# untitled.net
KiCad netlist of a schematic drawn in EAGLE
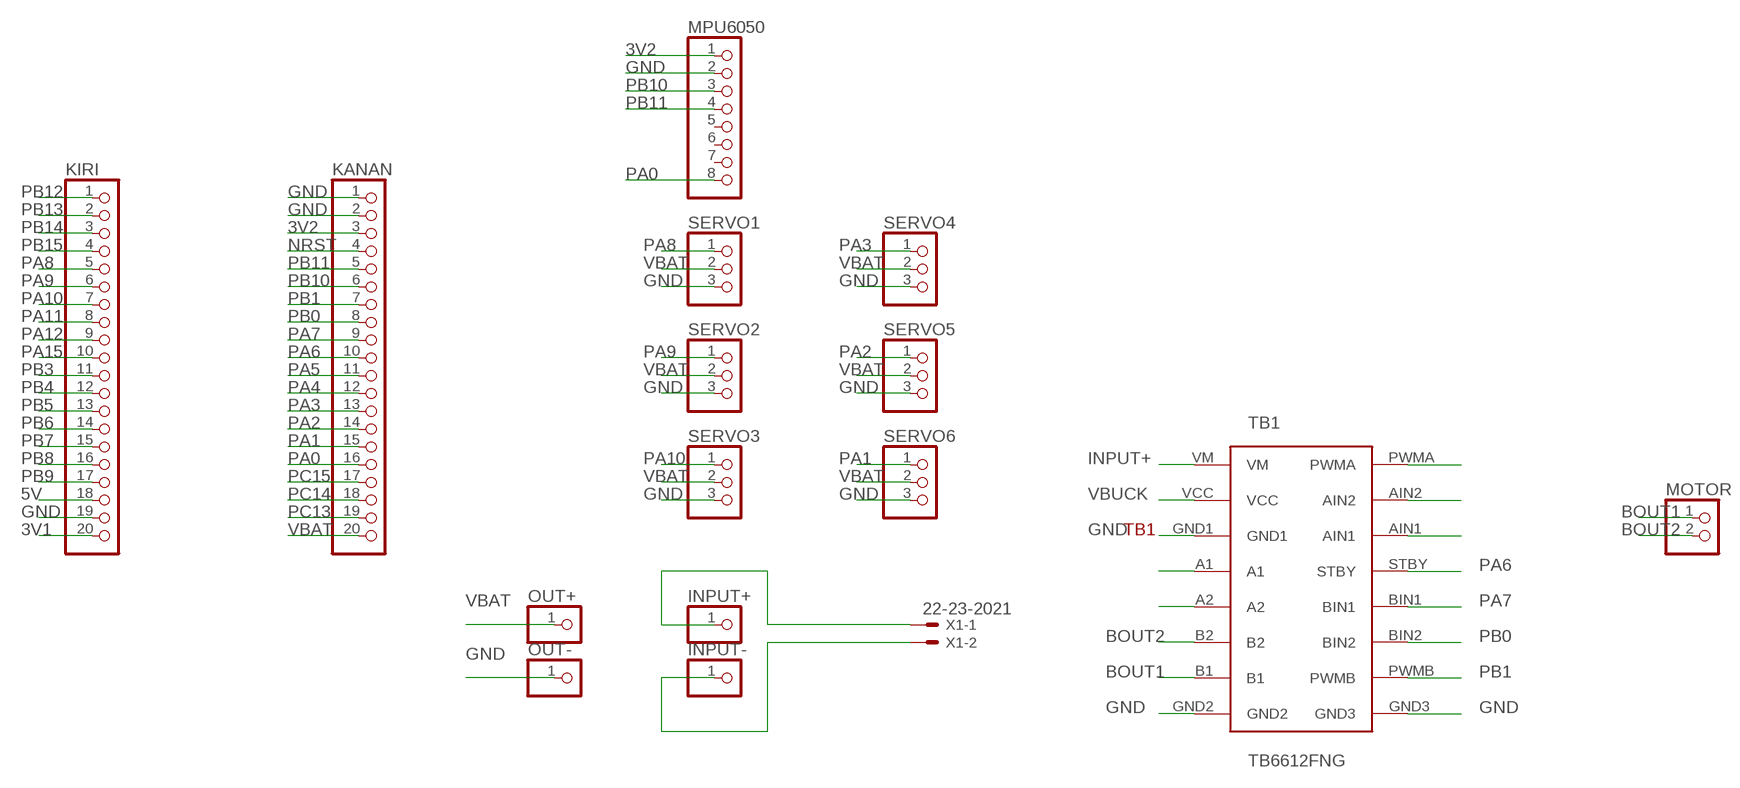
[diagram p0: schematic, sheet 1]

(export (version "E")
  (design (tool "Eeschema 10.0.6"))
  (components
    (comp (ref "INPUT+")
      (value "PINHD-1X1")
      (footprint "eagle-import:1X01")
      (libsource (lib "eagle-import") (part "PINHD-1X1"))
    )
    (comp (ref "INPUT-")
      (value "PINHD-1X1")
      (footprint "eagle-import:1X01")
      (libsource (lib "eagle-import") (part "PINHD-1X1"))
    )
    (comp (ref "KANAN")
      (value "PINHD-1X20")
      (footprint "eagle-import:1X20")
      (libsource (lib "eagle-import") (part "PINHD-1X20"))
    )
    (comp (ref "KIRI")
      (value "PINHD-1X20")
      (footprint "eagle-import:1X20")
      (libsource (lib "eagle-import") (part "PINHD-1X20"))
    )
    (comp (ref "MOTOR")
      (value "PINHD-1X2")
      (footprint "eagle-import:1X02")
      (libsource (lib "eagle-import") (part "PINHD-1X2"))
    )
    (comp (ref "MPU6050")
      (value "PINHD-1X8")
      (footprint "eagle-import:1X08")
      (libsource (lib "eagle-import") (part "PINHD-1X8"))
    )
    (comp (ref "OUT+")
      (value "PINHD-1X1")
      (footprint "eagle-import:1X01")
      (libsource (lib "eagle-import") (part "PINHD-1X1"))
    )
    (comp (ref "OUT-")
      (value "PINHD-1X1")
      (footprint "eagle-import:1X01")
      (libsource (lib "eagle-import") (part "PINHD-1X1"))
    )
    (comp (ref "SERVO1")
      (value "PINHD-1X3")
      (footprint "eagle-import:1X03")
      (libsource (lib "eagle-import") (part "PINHD-1X3"))
    )
    (comp (ref "SERVO2")
      (value "PINHD-1X3")
      (footprint "eagle-import:1X03")
      (libsource (lib "eagle-import") (part "PINHD-1X3"))
    )
    (comp (ref "SERVO3")
      (value "PINHD-1X3")
      (footprint "eagle-import:1X03")
      (libsource (lib "eagle-import") (part "PINHD-1X3"))
    )
    (comp (ref "SERVO4")
      (value "PINHD-1X3")
      (footprint "eagle-import:1X03")
      (libsource (lib "eagle-import") (part "PINHD-1X3"))
    )
    (comp (ref "SERVO5")
      (value "PINHD-1X3")
      (footprint "eagle-import:1X03")
      (libsource (lib "eagle-import") (part "PINHD-1X3"))
    )
    (comp (ref "SERVO6")
      (value "PINHD-1X3")
      (footprint "eagle-import:1X03")
      (libsource (lib "eagle-import") (part "PINHD-1X3"))
    )
    (comp (ref "TB1")
      (value "TB6612FNG")
      (footprint "eagle-import:TB6612FNG")
      (libsource (lib "eagle-import") (part "TB6612FNG"))
    )
    (comp (ref "X1")
      (value "22-23-2021")
      (footprint "eagle-import:22-23-2021")
      (fields (field (name "MF") "MOLEX"))
      (libsource (lib "eagle-import") (part "22-23-2021"))
    )
  )
  (nets
    (net (code "1") (name "/3V1") (class "Default")
      (node (ref "KIRI") (pin "20") (pinfunction "20_20") (pintype "passive"))
    )
    (net (code "2") (name "/3V2") (class "Default")
      (node (ref "KANAN") (pin "3") (pinfunction "3_3") (pintype "passive"))
      (node (ref "MPU6050") (pin "1") (pinfunction "1_1") (pintype "passive"))
    )
    (net (code "3") (name "/5V") (class "Default")
      (node (ref "KIRI") (pin "18") (pinfunction "18_18") (pintype "passive"))
    )
    (net (code "4") (name "/BOUT1") (class "Default")
      (node (ref "MOTOR") (pin "1") (pinfunction "1_1") (pintype "passive"))
      (node (ref "TB1") (pin "B1") (pinfunction "B1_B1") (pintype "bidirectional"))
    )
    (net (code "5") (name "/BOUT2") (class "Default")
      (node (ref "MOTOR") (pin "2") (pinfunction "2_2") (pintype "passive"))
      (node (ref "TB1") (pin "B2") (pinfunction "B2_B2") (pintype "bidirectional"))
    )
    (net (code "6") (name "/GND") (class "Default")
      (node (ref "KANAN") (pin "1") (pinfunction "1_1") (pintype "passive"))
      (node (ref "KANAN") (pin "2") (pinfunction "2_2") (pintype "passive"))
      (node (ref "KIRI") (pin "19") (pinfunction "19_19") (pintype "passive"))
      (node (ref "MPU6050") (pin "2") (pinfunction "2_2") (pintype "passive"))
      (node (ref "OUT-") (pin "1") (pinfunction "1_1") (pintype "passive"))
      (node (ref "SERVO1") (pin "3") (pinfunction "3_3") (pintype "passive"))
      (node (ref "SERVO2") (pin "3") (pinfunction "3_3") (pintype "passive"))
      (node (ref "SERVO3") (pin "3") (pinfunction "3_3") (pintype "passive"))
      (node (ref "SERVO4") (pin "3") (pinfunction "3_3") (pintype "passive"))
      (node (ref "SERVO5") (pin "3") (pinfunction "3_3") (pintype "passive"))
      (node (ref "SERVO6") (pin "3") (pinfunction "3_3") (pintype "passive"))
      (node (ref "TB1") (pin "GND1") (pinfunction "GND1_GND1") (pintype "bidirectional"))
      (node (ref "TB1") (pin "GND2") (pinfunction "GND2_GND2") (pintype "bidirectional"))
      (node (ref "TB1") (pin "GND3") (pinfunction "GND3_GND3") (pintype "bidirectional"))
    )
    (net (code "7") (name "/INPUT+") (class "Default")
      (node (ref "TB1") (pin "VM") (pinfunction "VM_VM") (pintype "bidirectional"))
    )
    (net (code "8") (name "/NRST") (class "Default")
      (node (ref "KANAN") (pin "4") (pinfunction "4_4") (pintype "passive"))
    )
    (net (code "9") (name "/PA0") (class "Default")
      (node (ref "KANAN") (pin "16") (pinfunction "16_16") (pintype "passive"))
      (node (ref "MPU6050") (pin "8") (pinfunction "8_8") (pintype "passive"))
    )
    (net (code "10") (name "/PA1") (class "Default")
      (node (ref "KANAN") (pin "15") (pinfunction "15_15") (pintype "passive"))
      (node (ref "SERVO6") (pin "1") (pinfunction "1_1") (pintype "passive"))
    )
    (net (code "11") (name "/PA2") (class "Default")
      (node (ref "KANAN") (pin "14") (pinfunction "14_14") (pintype "passive"))
      (node (ref "SERVO5") (pin "1") (pinfunction "1_1") (pintype "passive"))
    )
    (net (code "12") (name "/PA3") (class "Default")
      (node (ref "KANAN") (pin "13") (pinfunction "13_13") (pintype "passive"))
      (node (ref "SERVO4") (pin "1") (pinfunction "1_1") (pintype "passive"))
    )
    (net (code "13") (name "/PA4") (class "Default")
      (node (ref "KANAN") (pin "12") (pinfunction "12_12") (pintype "passive"))
    )
    (net (code "14") (name "/PA5") (class "Default")
      (node (ref "KANAN") (pin "11") (pinfunction "11_11") (pintype "passive"))
    )
    (net (code "15") (name "/PA6") (class "Default")
      (node (ref "KANAN") (pin "10") (pinfunction "10_10") (pintype "passive"))
      (node (ref "TB1") (pin "STBY") (pinfunction "STBY_STBY") (pintype "bidirectional"))
    )
    (net (code "16") (name "/PA7") (class "Default")
      (node (ref "KANAN") (pin "9") (pinfunction "9_9") (pintype "passive"))
      (node (ref "TB1") (pin "BIN1") (pinfunction "BIN1_BIN1") (pintype "bidirectional"))
    )
    (net (code "17") (name "/PA8") (class "Default")
      (node (ref "KIRI") (pin "5") (pinfunction "5_5") (pintype "passive"))
      (node (ref "SERVO1") (pin "1") (pinfunction "1_1") (pintype "passive"))
    )
    (net (code "18") (name "/PA9") (class "Default")
      (node (ref "KIRI") (pin "6") (pinfunction "6_6") (pintype "passive"))
      (node (ref "SERVO2") (pin "1") (pinfunction "1_1") (pintype "passive"))
    )
    (net (code "19") (name "/PA10") (class "Default")
      (node (ref "KIRI") (pin "7") (pinfunction "7_7") (pintype "passive"))
      (node (ref "SERVO3") (pin "1") (pinfunction "1_1") (pintype "passive"))
    )
    (net (code "20") (name "/PA11") (class "Default")
      (node (ref "KIRI") (pin "8") (pinfunction "8_8") (pintype "passive"))
    )
    (net (code "21") (name "/PA12") (class "Default")
      (node (ref "KIRI") (pin "9") (pinfunction "9_9") (pintype "passive"))
    )
    (net (code "22") (name "/PA15") (class "Default")
      (node (ref "KIRI") (pin "10") (pinfunction "10_10") (pintype "passive"))
    )
    (net (code "23") (name "/PB0") (class "Default")
      (node (ref "KANAN") (pin "8") (pinfunction "8_8") (pintype "passive"))
      (node (ref "TB1") (pin "BIN2") (pinfunction "BIN2_BIN2") (pintype "bidirectional"))
    )
    (net (code "24") (name "/PB1") (class "Default")
      (node (ref "KANAN") (pin "7") (pinfunction "7_7") (pintype "passive"))
      (node (ref "TB1") (pin "PWMB") (pinfunction "PWMB_PWMB") (pintype "bidirectional"))
    )
    (net (code "25") (name "/PB3") (class "Default")
      (node (ref "KIRI") (pin "11") (pinfunction "11_11") (pintype "passive"))
    )
    (net (code "26") (name "/PB4") (class "Default")
      (node (ref "KIRI") (pin "12") (pinfunction "12_12") (pintype "passive"))
    )
    (net (code "27") (name "/PB5") (class "Default")
      (node (ref "KIRI") (pin "13") (pinfunction "13_13") (pintype "passive"))
    )
    (net (code "28") (name "/PB6") (class "Default")
      (node (ref "KIRI") (pin "14") (pinfunction "14_14") (pintype "passive"))
    )
    (net (code "29") (name "/PB7") (class "Default")
      (node (ref "KIRI") (pin "15") (pinfunction "15_15") (pintype "passive"))
    )
    (net (code "30") (name "/PB8") (class "Default")
      (node (ref "KIRI") (pin "16") (pinfunction "16_16") (pintype "passive"))
    )
    (net (code "31") (name "/PB9") (class "Default")
      (node (ref "KIRI") (pin "17") (pinfunction "17_17") (pintype "passive"))
    )
    (net (code "32") (name "/PB10") (class "Default")
      (node (ref "KANAN") (pin "6") (pinfunction "6_6") (pintype "passive"))
      (node (ref "MPU6050") (pin "3") (pinfunction "3_3") (pintype "passive"))
    )
    (net (code "33") (name "/PB11") (class "Default")
      (node (ref "KANAN") (pin "5") (pinfunction "5_5") (pintype "passive"))
      (node (ref "MPU6050") (pin "4") (pinfunction "4_4") (pintype "passive"))
    )
    (net (code "34") (name "/PB12") (class "Default")
      (node (ref "KIRI") (pin "1") (pinfunction "1_1") (pintype "passive"))
    )
    (net (code "35") (name "/PB13") (class "Default")
      (node (ref "KIRI") (pin "2") (pinfunction "2_2") (pintype "passive"))
    )
    (net (code "36") (name "/PB14") (class "Default")
      (node (ref "KIRI") (pin "3") (pinfunction "3_3") (pintype "passive"))
    )
    (net (code "37") (name "/PB15") (class "Default")
      (node (ref "KIRI") (pin "4") (pinfunction "4_4") (pintype "passive"))
    )
    (net (code "38") (name "/PC13") (class "Default")
      (node (ref "KANAN") (pin "19") (pinfunction "19_19") (pintype "passive"))
    )
    (net (code "39") (name "/PC14") (class "Default")
      (node (ref "KANAN") (pin "18") (pinfunction "18_18") (pintype "passive"))
    )
    (net (code "40") (name "/PC15") (class "Default")
      (node (ref "KANAN") (pin "17") (pinfunction "17_17") (pintype "passive"))
    )
    (net (code "41") (name "/VBAT") (class "Default")
      (node (ref "KANAN") (pin "20") (pinfunction "20_20") (pintype "passive"))
      (node (ref "OUT+") (pin "1") (pinfunction "1_1") (pintype "passive"))
      (node (ref "SERVO1") (pin "2") (pinfunction "2_2") (pintype "passive"))
      (node (ref "SERVO2") (pin "2") (pinfunction "2_2") (pintype "passive"))
      (node (ref "SERVO3") (pin "2") (pinfunction "2_2") (pintype "passive"))
      (node (ref "SERVO4") (pin "2") (pinfunction "2_2") (pintype "passive"))
      (node (ref "SERVO5") (pin "2") (pinfunction "2_2") (pintype "passive"))
      (node (ref "SERVO6") (pin "2") (pinfunction "2_2") (pintype "passive"))
    )
    (net (code "42") (name "/VBUCK") (class "Default")
      (node (ref "TB1") (pin "VCC") (pinfunction "VCC_VCC") (pintype "bidirectional"))
    )
    (net (code "43") (name "Net-(X1A-S)") (class "Default")
      (node (ref "INPUT+") (pin "1") (pinfunction "1_1") (pintype "passive"))
      (node (ref "X1") (pin "1") (pinfunction "S_1") (pintype "passive"))
    )
    (net (code "44") (name "Net-(X1B-S)") (class "Default")
      (node (ref "INPUT-") (pin "1") (pinfunction "1_1") (pintype "passive"))
      (node (ref "X1") (pin "2") (pinfunction "S_2") (pintype "passive"))
    )
    (net (code "45") (name "unconnected-(MPU6050-Pad5)") (class "Default")
      (node (ref "MPU6050") (pin "5") (pinfunction "5_5") (pintype "passive"))
    )
    (net (code "46") (name "unconnected-(MPU6050-Pad6)") (class "Default")
      (node (ref "MPU6050") (pin "6") (pinfunction "6_6") (pintype "passive"))
    )
    (net (code "47") (name "unconnected-(MPU6050-Pad7)") (class "Default")
      (node (ref "MPU6050") (pin "7") (pinfunction "7_7") (pintype "passive"))
    )
    (net (code "48") (name "unconnected-(TB1-PadA1)") (class "Default")
      (node (ref "TB1") (pin "A1") (pinfunction "A1_A1") (pintype "bidirectional"))
    )
    (net (code "49") (name "unconnected-(TB1-PadA2)") (class "Default")
      (node (ref "TB1") (pin "A2") (pinfunction "A2_A2") (pintype "bidirectional"))
    )
    (net (code "50") (name "unconnected-(TB1-PadAIN1)") (class "Default")
      (node (ref "TB1") (pin "AIN1") (pinfunction "AIN1_AIN1") (pintype "bidirectional"))
    )
    (net (code "51") (name "unconnected-(TB1-PadAIN2)") (class "Default")
      (node (ref "TB1") (pin "AIN2") (pinfunction "AIN2_AIN2") (pintype "bidirectional"))
    )
    (net (code "52") (name "unconnected-(TB1-PadPWMA)") (class "Default")
      (node (ref "TB1") (pin "PWMA") (pinfunction "PWMA_PWMA") (pintype "bidirectional"))
    )
  )
)
